# vca_A.net
KiCad netlist of a schematic drawn in Altium Designer
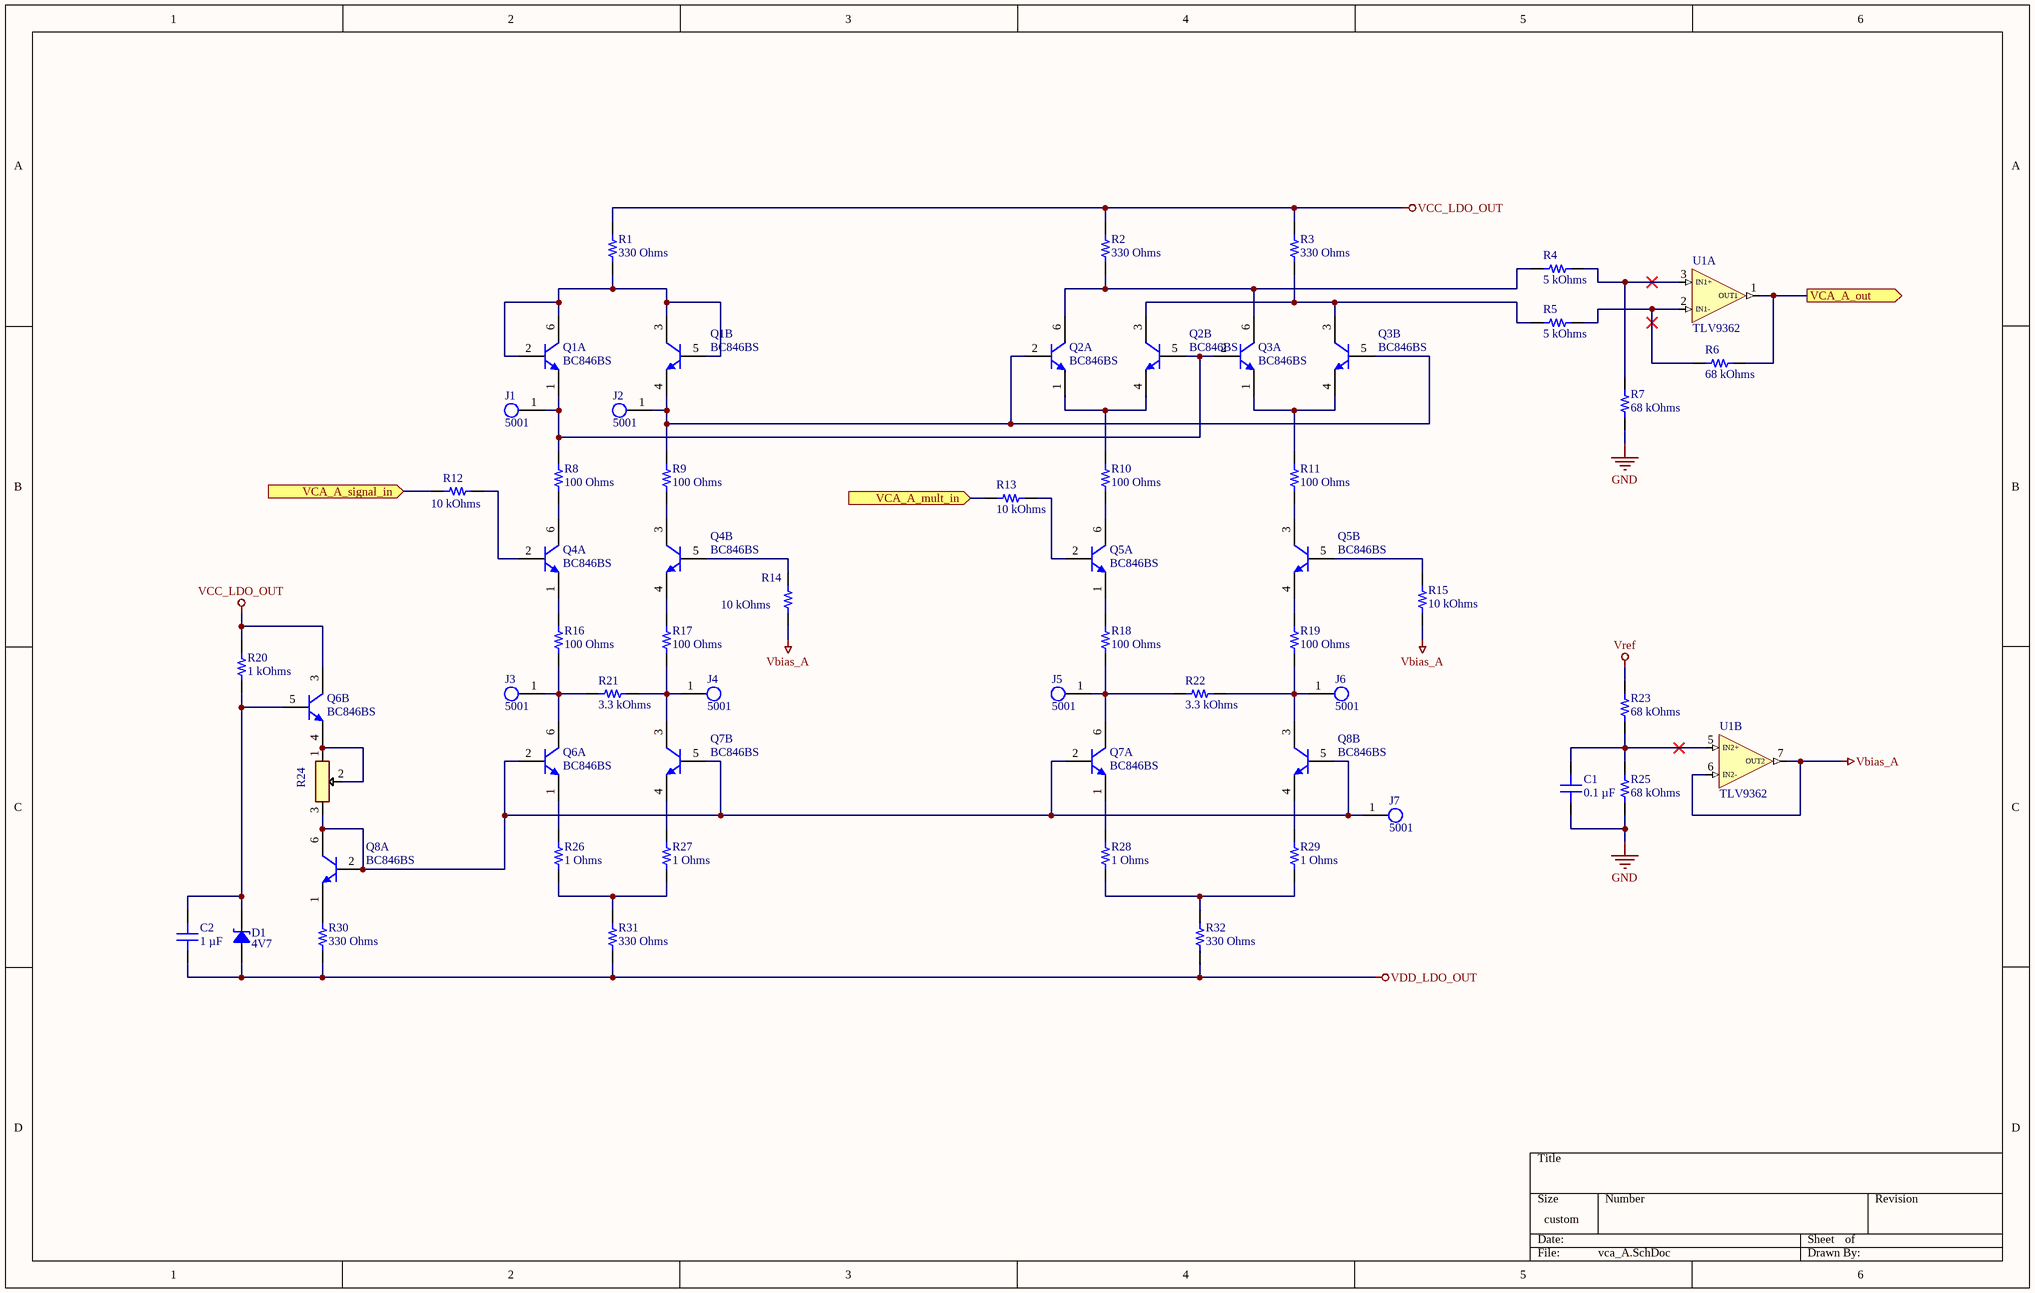
[diagram p0: vca_A.SchDoc]

(export (version "E")
  (design (tool "Eeschema 10.0.6"))
  (components
    (comp (ref "C1")
      (value "0.1 µF")
      (footprint "CAP 1206_3216 - 0.8MM")
      (description "CAP CER 0.1UF 50V X7R 1206")
      (fields
        (field (name "PART NUMBER") "885012208087")
        (field (name "CAPACITANCE") "0.1 µF")
        (field (name "MANUFACTURER") "Würth Elektronik")
      )
      (libsource (lib "Celestial Altium Library - altium_library") (part "Capacitor"))
    )
    (comp (ref "C2")
      (value "1 µF")
      (footprint "CAP 1206_3216 - 0.8MM")
      (description "CAP CER 1UF 50V X7R 1206")
      (fields
        (field (name "PART NUMBER") "885012208093")
        (field (name "CAPACITANCE") "1 µF")
        (field (name "MANUFACTURER") "Würth Elektronik")
      )
      (libsource (lib "Celestial Altium Library - altium_library") (part "Capacitor"))
    )
    (comp (ref "D1") (value "4V7") (footprint "SOD323") (libsource (lib "za_koncar") (part "BZX38450-C4V7X")))
    (comp (ref "J1")
      (value "5001")
      (footprint "FP-5001-MFG")
      (description "PC TEST POINT MINIATURE BLACK")
      (libsource (lib "za_koncar") (part "CMP-2000-05181-2"))
    )
    (comp (ref "J2")
      (value "5001")
      (footprint "FP-5001-MFG")
      (description "PC TEST POINT MINIATURE BLACK")
      (libsource (lib "za_koncar") (part "CMP-2000-05181-2"))
    )
    (comp (ref "J3")
      (value "5001")
      (footprint "FP-5001-MFG")
      (description "PC TEST POINT MINIATURE BLACK")
      (libsource (lib "za_koncar") (part "CMP-2000-05181-2"))
    )
    (comp (ref "J4")
      (value "5001")
      (footprint "FP-5001-MFG")
      (description "PC TEST POINT MINIATURE BLACK")
      (libsource (lib "za_koncar") (part "CMP-2000-05181-2"))
    )
    (comp (ref "J5")
      (value "5001")
      (footprint "FP-5001-MFG")
      (description "PC TEST POINT MINIATURE BLACK")
      (libsource (lib "za_koncar") (part "CMP-2000-05181-2"))
    )
    (comp (ref "J6")
      (value "5001")
      (footprint "FP-5001-MFG")
      (description "PC TEST POINT MINIATURE BLACK")
      (libsource (lib "za_koncar") (part "CMP-2000-05181-2"))
    )
    (comp (ref "J7")
      (value "5001")
      (footprint "FP-5001-MFG")
      (description "PC TEST POINT MINIATURE BLACK")
      (libsource (lib "za_koncar") (part "CMP-2000-05181-2"))
    )
    (comp (ref "Q1")
      (value "BC846BS")
      (footprint "TSOP65P210X110-6N")
      (description "65 V, 100 mA matched NPN/NPN general-purpose transistor")
      (libsource (lib "za_koncar") (part "BC846BS"))
    )
    (comp (ref "Q2")
      (value "BC846BS")
      (footprint "TSOP65P210X110-6N")
      (description "65 V, 100 mA matched NPN/NPN general-purpose transistor")
      (libsource (lib "za_koncar") (part "BC846BS"))
    )
    (comp (ref "Q3")
      (value "BC846BS")
      (footprint "TSOP65P210X110-6N")
      (description "65 V, 100 mA matched NPN/NPN general-purpose transistor")
      (libsource (lib "za_koncar") (part "BC846BS"))
    )
    (comp (ref "Q4")
      (value "BC846BS")
      (footprint "TSOP65P210X110-6N")
      (description "65 V, 100 mA matched NPN/NPN general-purpose transistor")
      (libsource (lib "za_koncar") (part "BC846BS"))
    )
    (comp (ref "Q5")
      (value "BC846BS")
      (footprint "TSOP65P210X110-6N")
      (description "65 V, 100 mA matched NPN/NPN general-purpose transistor")
      (libsource (lib "za_koncar") (part "BC846BS"))
    )
    (comp (ref "Q6")
      (value "BC846BS")
      (footprint "TSOP65P210X110-6N")
      (description "65 V, 100 mA matched NPN/NPN general-purpose transistor")
      (libsource (lib "za_koncar") (part "BC846BS"))
    )
    (comp (ref "Q7")
      (value "BC846BS")
      (footprint "TSOP65P210X110-6N")
      (description "65 V, 100 mA matched NPN/NPN general-purpose transistor")
      (libsource (lib "za_koncar") (part "BC846BS"))
    )
    (comp (ref "Q8")
      (value "BC846BS")
      (footprint "TSOP65P210X110-6N")
      (description "65 V, 100 mA matched NPN/NPN general-purpose transistor")
      (libsource (lib "za_koncar") (part "BC846BS"))
    )
    (comp (ref "R1")
      (value "330 Ohms")
      (footprint "YAGEO RES 1206_3216")
      (description "RES SMD 330 OHM 1% 1/4W 1206")
      (fields (field (name "PART NUMBER") "RT1206FRD07330RL") (field (name "MANUFACTURER") "Yageo"))
      (libsource (lib "Celestial Altium Library - altium_library") (part "Resistor"))
    )
    (comp (ref "R2")
      (value "330 Ohms")
      (footprint "YAGEO RES 1206_3216")
      (description "RES SMD 330 OHM 1% 1/4W 1206")
      (fields (field (name "PART NUMBER") "RT1206FRD07330RL") (field (name "MANUFACTURER") "Yageo"))
      (libsource (lib "Celestial Altium Library - altium_library") (part "Resistor"))
    )
    (comp (ref "R3")
      (value "330 Ohms")
      (footprint "YAGEO RES 1206_3216")
      (description "RES SMD 330 OHM 1% 1/4W 1206")
      (fields (field (name "PART NUMBER") "RT1206FRD07330RL") (field (name "MANUFACTURER") "Yageo"))
      (libsource (lib "Celestial Altium Library - altium_library") (part "Resistor"))
    )
    (comp (ref "R4")
      (value "5 kOhms")
      (footprint "YAGEO RES 1206_3216")
      (description "RES 5K OHM 1% 1/4W 1206")
      (fields (field (name "PART NUMBER") "RT1206FRE075KL") (field (name "MANUFACTURER") "Yageo"))
      (libsource (lib "Celestial Altium Library - altium_library") (part "Resistor"))
    )
    (comp (ref "R5")
      (value "5 kOhms")
      (footprint "YAGEO RES 1206_3216")
      (description "RES 5K OHM 1% 1/4W 1206")
      (fields (field (name "PART NUMBER") "RT1206FRE075KL") (field (name "MANUFACTURER") "Yageo"))
      (libsource (lib "Celestial Altium Library - altium_library") (part "Resistor"))
    )
    (comp (ref "R6")
      (value "68 kOhms")
      (footprint "YAGEO RES 1206_3216")
      (description "RES SMD 68K OHM 1% 1/4W 1206")
      (fields (field (name "PART NUMBER") "RT1206FRE0768KL") (field (name "MANUFACTURER") "Yageo"))
      (libsource (lib "Celestial Altium Library - altium_library") (part "Resistor"))
    )
    (comp (ref "R7")
      (value "68 kOhms")
      (footprint "YAGEO RES 1206_3216")
      (description "RES SMD 68K OHM 1% 1/4W 1206")
      (fields (field (name "PART NUMBER") "RT1206FRE0768KL") (field (name "MANUFACTURER") "Yageo"))
      (libsource (lib "Celestial Altium Library - altium_library") (part "Resistor"))
    )
    (comp (ref "R8")
      (value "100 Ohms")
      (footprint "YAGEO RES 1206_3216")
      (description "RES SMD 100 OHM 1% 1/4W 1206")
      (fields (field (name "PART NUMBER") "RT1206FRD07100RL") (field (name "MANUFACTURER") "Yageo"))
      (libsource (lib "Celestial Altium Library - altium_library") (part "Resistor"))
    )
    (comp (ref "R9")
      (value "100 Ohms")
      (footprint "YAGEO RES 1206_3216")
      (description "RES SMD 100 OHM 1% 1/4W 1206")
      (fields (field (name "PART NUMBER") "RT1206FRD07100RL") (field (name "MANUFACTURER") "Yageo"))
      (libsource (lib "Celestial Altium Library - altium_library") (part "Resistor"))
    )
    (comp (ref "R10")
      (value "100 Ohms")
      (footprint "YAGEO RES 1206_3216")
      (description "RES SMD 100 OHM 1% 1/4W 1206")
      (fields (field (name "PART NUMBER") "RT1206FRD07100RL") (field (name "MANUFACTURER") "Yageo"))
      (libsource (lib "Celestial Altium Library - altium_library") (part "Resistor"))
    )
    (comp (ref "R11")
      (value "100 Ohms")
      (footprint "YAGEO RES 1206_3216")
      (description "RES SMD 100 OHM 1% 1/4W 1206")
      (fields (field (name "PART NUMBER") "RT1206FRD07100RL") (field (name "MANUFACTURER") "Yageo"))
      (libsource (lib "Celestial Altium Library - altium_library") (part "Resistor"))
    )
    (comp (ref "R12")
      (value "10 kOhms")
      (footprint "YAGEO RES 1206_3216")
      (description "RES SMD 10K OHM 1% 1/4W 1206")
      (fields (field (name "PART NUMBER") "RT1206FRE0710KL") (field (name "MANUFACTURER") "Yageo"))
      (libsource (lib "Celestial Altium Library - altium_library") (part "Resistor"))
    )
    (comp (ref "R13")
      (value "10 kOhms")
      (footprint "YAGEO RES 1206_3216")
      (description "RES SMD 10K OHM 1% 1/4W 1206")
      (fields (field (name "PART NUMBER") "RT1206FRE0710KL") (field (name "MANUFACTURER") "Yageo"))
      (libsource (lib "Celestial Altium Library - altium_library") (part "Resistor"))
    )
    (comp (ref "R14")
      (value "10 kOhms")
      (footprint "YAGEO RES 1206_3216")
      (description "RES SMD 10K OHM 1% 1/4W 1206")
      (fields (field (name "PART NUMBER") "RT1206FRE0710KL") (field (name "MANUFACTURER") "Yageo"))
      (libsource (lib "Celestial Altium Library - altium_library") (part "Resistor"))
    )
    (comp (ref "R15")
      (value "10 kOhms")
      (footprint "YAGEO RES 1206_3216")
      (description "RES SMD 10K OHM 1% 1/4W 1206")
      (fields (field (name "PART NUMBER") "RT1206FRE0710KL") (field (name "MANUFACTURER") "Yageo"))
      (libsource (lib "Celestial Altium Library - altium_library") (part "Resistor"))
    )
    (comp (ref "R16")
      (value "100 Ohms")
      (footprint "YAGEO RES 1206_3216")
      (description "RES SMD 100 OHM 1% 1/4W 1206")
      (fields (field (name "PART NUMBER") "RT1206FRD07100RL") (field (name "MANUFACTURER") "Yageo"))
      (libsource (lib "Celestial Altium Library - altium_library") (part "Resistor"))
    )
    (comp (ref "R17")
      (value "100 Ohms")
      (footprint "YAGEO RES 1206_3216")
      (description "RES SMD 100 OHM 1% 1/4W 1206")
      (fields (field (name "PART NUMBER") "RT1206FRD07100RL") (field (name "MANUFACTURER") "Yageo"))
      (libsource (lib "Celestial Altium Library - altium_library") (part "Resistor"))
    )
    (comp (ref "R18")
      (value "100 Ohms")
      (footprint "YAGEO RES 1206_3216")
      (description "RES SMD 100 OHM 1% 1/4W 1206")
      (fields (field (name "PART NUMBER") "RT1206FRD07100RL") (field (name "MANUFACTURER") "Yageo"))
      (libsource (lib "Celestial Altium Library - altium_library") (part "Resistor"))
    )
    (comp (ref "R19")
      (value "100 Ohms")
      (footprint "YAGEO RES 1206_3216")
      (description "RES SMD 100 OHM 1% 1/4W 1206")
      (fields (field (name "PART NUMBER") "RT1206FRD07100RL") (field (name "MANUFACTURER") "Yageo"))
      (libsource (lib "Celestial Altium Library - altium_library") (part "Resistor"))
    )
    (comp (ref "R20")
      (value "1 kOhms")
      (footprint "YAGEO RES 1206_3216")
      (description "RES SMD 1K OHM 1% 1/4W 1206")
      (fields (field (name "PART NUMBER") "RT1206FRE071KL") (field (name "MANUFACTURER") "Yageo"))
      (libsource (lib "Celestial Altium Library - altium_library") (part "Resistor"))
    )
    (comp (ref "R21")
      (value "3.3 kOhms")
      (footprint "YAGEO RES 1206_3216")
      (description "RES SMD 3.3K OHM 1% 1/4W 1206")
      (fields (field (name "PART NUMBER") "RT1206FRE073K3L") (field (name "MANUFACTURER") "Yageo"))
      (libsource (lib "Celestial Altium Library - altium_library") (part "Resistor"))
    )
    (comp (ref "R22")
      (value "3.3 kOhms")
      (footprint "YAGEO RES 1206_3216")
      (description "RES SMD 3.3K OHM 1% 1/4W 1206")
      (fields (field (name "PART NUMBER") "RT1206FRE073K3L") (field (name "MANUFACTURER") "Yageo"))
      (libsource (lib "Celestial Altium Library - altium_library") (part "Resistor"))
    )
    (comp (ref "R23")
      (value "68 kOhms")
      (footprint "YAGEO RES 1206_3216")
      (description "RES SMD 68K OHM 1% 1/4W 1206")
      (fields (field (name "PART NUMBER") "RT1206FRE0768KL") (field (name "MANUFACTURER") "Yageo"))
      (libsource (lib "Celestial Altium Library - altium_library") (part "Resistor"))
    )
    (comp (ref "R24")
      (value "TC33X-2-502G")
      (footprint "TC33X2503E")
      (description "Resistor")
      (fields (field (name "MOUSER PART NUMBER") "652-TC33X-2-502G"))
      (libsource (lib "za_koncar") (part "TC33X-2-502G"))
    )
    (comp (ref "R25")
      (value "68 kOhms")
      (footprint "YAGEO RES 1206_3216")
      (description "RES SMD 68K OHM 1% 1/4W 1206")
      (fields (field (name "PART NUMBER") "RT1206FRE0768KL") (field (name "MANUFACTURER") "Yageo"))
      (libsource (lib "Celestial Altium Library - altium_library") (part "Resistor"))
    )
    (comp (ref "R26")
      (value "1 Ohms")
      (footprint "YAGEO RES 1206_3216")
      (description "RES 1 OHM 0.1% 1/4W 1206")
      (fields (field (name "PART NUMBER") "RT1206BRD071RL") (field (name "MANUFACTURER") "Yageo"))
      (libsource (lib "Celestial Altium Library - altium_library") (part "Resistor"))
    )
    (comp (ref "R27")
      (value "1 Ohms")
      (footprint "YAGEO RES 1206_3216")
      (description "RES 1 OHM 0.1% 1/4W 1206")
      (fields (field (name "PART NUMBER") "RT1206BRD071RL") (field (name "MANUFACTURER") "Yageo"))
      (libsource (lib "Celestial Altium Library - altium_library") (part "Resistor"))
    )
    (comp (ref "R28")
      (value "1 Ohms")
      (footprint "YAGEO RES 1206_3216")
      (description "RES 1 OHM 0.1% 1/4W 1206")
      (fields (field (name "PART NUMBER") "RT1206BRD071RL") (field (name "MANUFACTURER") "Yageo"))
      (libsource (lib "Celestial Altium Library - altium_library") (part "Resistor"))
    )
    (comp (ref "R29")
      (value "1 Ohms")
      (footprint "YAGEO RES 1206_3216")
      (description "RES 1 OHM 0.1% 1/4W 1206")
      (fields (field (name "PART NUMBER") "RT1206BRD071RL") (field (name "MANUFACTURER") "Yageo"))
      (libsource (lib "Celestial Altium Library - altium_library") (part "Resistor"))
    )
    (comp (ref "R30")
      (value "330 Ohms")
      (footprint "YAGEO RES 1206_3216")
      (description "RES SMD 330 OHM 1% 1/4W 1206")
      (fields (field (name "PART NUMBER") "RT1206FRD07330RL") (field (name "MANUFACTURER") "Yageo"))
      (libsource (lib "Celestial Altium Library - altium_library") (part "Resistor"))
    )
    (comp (ref "R31")
      (value "330 Ohms")
      (footprint "YAGEO RES 1206_3216")
      (description "RES SMD 330 OHM 1% 1/4W 1206")
      (fields (field (name "PART NUMBER") "RT1206FRD07330RL") (field (name "MANUFACTURER") "Yageo"))
      (libsource (lib "Celestial Altium Library - altium_library") (part "Resistor"))
    )
    (comp (ref "R32")
      (value "330 Ohms")
      (footprint "YAGEO RES 1206_3216")
      (description "RES SMD 330 OHM 1% 1/4W 1206")
      (fields (field (name "PART NUMBER") "RT1206FRD07330RL") (field (name "MANUFACTURER") "Yageo"))
      (libsource (lib "Celestial Altium Library - altium_library") (part "Resistor"))
    )
    (comp (ref "U1")
      (value "TLV9362")
      (footprint "SOIC8-127P600X175-8N")
      (description "TLV936x 10-MHz, 40-V, RRO, Operational Amplifie")
      (libsource (lib "za_koncar") (part "TLV9362"))
    )
  )
  (nets
    (net (code "1") (name "/VCA_A_mult_in") (class "Default")
      (node (ref "R13") (pin "1") (pinfunction "1_1") (pintype "passive"))
    )
    (net (code "2") (name "/VCA_A_out") (class "Default")
      (node (ref "R6") (pin "1") (pinfunction "1_1") (pintype "passive"))
      (node (ref "U1") (pin "1") (pinfunction "OUT1_1") (pintype "output"))
    )
    (net (code "3") (name "/VCA_A_signal_in") (class "Default")
      (node (ref "R12") (pin "1") (pinfunction "1_1") (pintype "passive"))
    )
    (net (code "4") (name "GND") (class "Default")
      (node (ref "C1") (pin "1") (pinfunction "1_1") (pintype "passive"))
      (node (ref "R25") (pin "1") (pinfunction "1_1") (pintype "passive"))
      (node (ref "R7") (pin "2") (pinfunction "2_2") (pintype "passive"))
    )
    (net (code "5") (name "Net-(Q1A-B1)") (class "Default")
      (node (ref "Q1") (pin "2") (pinfunction "B1_2") (pintype "passive"))
      (node (ref "Q1") (pin "3") (pinfunction "C2_3") (pintype "passive"))
      (node (ref "Q1") (pin "5") (pinfunction "B2_5") (pintype "passive"))
      (node (ref "Q1") (pin "6") (pinfunction "C1_6") (pintype "passive"))
      (node (ref "R1") (pin "1") (pinfunction "1_1") (pintype "passive"))
    )
    (net (code "6") (name "Net-(Q1A-E1)") (class "Default")
      (node (ref "J1") (pin "1") (pinfunction "1_1") (pintype "passive"))
      (node (ref "Q1") (pin "1") (pinfunction "E1_1") (pintype "passive"))
      (node (ref "Q2") (pin "5") (pinfunction "B2_5") (pintype "passive"))
      (node (ref "Q3") (pin "2") (pinfunction "B1_2") (pintype "passive"))
      (node (ref "R8") (pin "2") (pinfunction "2_2") (pintype "passive"))
    )
    (net (code "7") (name "Net-(Q1B-E2)") (class "Default")
      (node (ref "J2") (pin "1") (pinfunction "1_1") (pintype "passive"))
      (node (ref "Q1") (pin "4") (pinfunction "E2_4") (pintype "passive"))
      (node (ref "Q2") (pin "2") (pinfunction "B1_2") (pintype "passive"))
      (node (ref "Q3") (pin "5") (pinfunction "B2_5") (pintype "passive"))
      (node (ref "R9") (pin "2") (pinfunction "2_2") (pintype "passive"))
    )
    (net (code "8") (name "Net-(Q2A-C1)") (class "Default")
      (node (ref "Q2") (pin "6") (pinfunction "C1_6") (pintype "passive"))
      (node (ref "Q3") (pin "6") (pinfunction "C1_6") (pintype "passive"))
      (node (ref "R2") (pin "1") (pinfunction "1_1") (pintype "passive"))
      (node (ref "R4") (pin "2") (pinfunction "2_2") (pintype "passive"))
    )
    (net (code "9") (name "Net-(Q2A-E1)") (class "Default")
      (node (ref "Q2") (pin "1") (pinfunction "E1_1") (pintype "passive"))
      (node (ref "Q2") (pin "4") (pinfunction "E2_4") (pintype "passive"))
      (node (ref "R10") (pin "2") (pinfunction "2_2") (pintype "passive"))
    )
    (net (code "10") (name "Net-(Q2B-C2)") (class "Default")
      (node (ref "Q2") (pin "3") (pinfunction "C2_3") (pintype "passive"))
      (node (ref "Q3") (pin "3") (pinfunction "C2_3") (pintype "passive"))
      (node (ref "R3") (pin "1") (pinfunction "1_1") (pintype "passive"))
      (node (ref "R5") (pin "2") (pinfunction "2_2") (pintype "passive"))
    )
    (net (code "11") (name "Net-(Q3A-E1)") (class "Default")
      (node (ref "Q3") (pin "1") (pinfunction "E1_1") (pintype "passive"))
      (node (ref "Q3") (pin "4") (pinfunction "E2_4") (pintype "passive"))
      (node (ref "R11") (pin "2") (pinfunction "2_2") (pintype "passive"))
    )
    (net (code "12") (name "Net-(Q4A-B1)") (class "Default")
      (node (ref "Q4") (pin "2") (pinfunction "B1_2") (pintype "passive"))
      (node (ref "R12") (pin "2") (pinfunction "2_2") (pintype "passive"))
    )
    (net (code "13") (name "Net-(Q4A-C1)") (class "Default")
      (node (ref "Q4") (pin "6") (pinfunction "C1_6") (pintype "passive"))
      (node (ref "R8") (pin "1") (pinfunction "1_1") (pintype "passive"))
    )
    (net (code "14") (name "Net-(Q4A-E1)") (class "Default")
      (node (ref "Q4") (pin "1") (pinfunction "E1_1") (pintype "passive"))
      (node (ref "R16") (pin "2") (pinfunction "2_2") (pintype "passive"))
    )
    (net (code "15") (name "Net-(Q4B-B2)") (class "Default")
      (node (ref "Q4") (pin "5") (pinfunction "B2_5") (pintype "passive"))
      (node (ref "R14") (pin "2") (pinfunction "2_2") (pintype "passive"))
    )
    (net (code "16") (name "Net-(Q4B-C2)") (class "Default")
      (node (ref "Q4") (pin "3") (pinfunction "C2_3") (pintype "passive"))
      (node (ref "R9") (pin "1") (pinfunction "1_1") (pintype "passive"))
    )
    (net (code "17") (name "Net-(Q4B-E2)") (class "Default")
      (node (ref "Q4") (pin "4") (pinfunction "E2_4") (pintype "passive"))
      (node (ref "R17") (pin "2") (pinfunction "2_2") (pintype "passive"))
    )
    (net (code "18") (name "Net-(Q5A-B1)") (class "Default")
      (node (ref "Q5") (pin "2") (pinfunction "B1_2") (pintype "passive"))
      (node (ref "R13") (pin "2") (pinfunction "2_2") (pintype "passive"))
    )
    (net (code "19") (name "Net-(Q5A-C1)") (class "Default")
      (node (ref "Q5") (pin "6") (pinfunction "C1_6") (pintype "passive"))
      (node (ref "R10") (pin "1") (pinfunction "1_1") (pintype "passive"))
    )
    (net (code "20") (name "Net-(Q5A-E1)") (class "Default")
      (node (ref "Q5") (pin "1") (pinfunction "E1_1") (pintype "passive"))
      (node (ref "R18") (pin "2") (pinfunction "2_2") (pintype "passive"))
    )
    (net (code "21") (name "Net-(Q5B-B2)") (class "Default")
      (node (ref "Q5") (pin "5") (pinfunction "B2_5") (pintype "passive"))
      (node (ref "R15") (pin "2") (pinfunction "2_2") (pintype "passive"))
    )
    (net (code "22") (name "Net-(Q5B-C2)") (class "Default")
      (node (ref "Q5") (pin "3") (pinfunction "C2_3") (pintype "passive"))
      (node (ref "R11") (pin "1") (pinfunction "1_1") (pintype "passive"))
    )
    (net (code "23") (name "Net-(Q5B-E2)") (class "Default")
      (node (ref "Q5") (pin "4") (pinfunction "E2_4") (pintype "passive"))
      (node (ref "R19") (pin "2") (pinfunction "2_2") (pintype "passive"))
    )
    (net (code "24") (name "Net-(Q6A-B1)") (class "Default")
      (node (ref "J7") (pin "1") (pinfunction "1_1") (pintype "passive"))
      (node (ref "Q6") (pin "2") (pinfunction "B1_2") (pintype "passive"))
      (node (ref "Q7") (pin "2") (pinfunction "B1_2") (pintype "passive"))
      (node (ref "Q7") (pin "5") (pinfunction "B2_5") (pintype "passive"))
      (node (ref "Q8") (pin "2") (pinfunction "B1_2") (pintype "passive"))
      (node (ref "Q8") (pin "5") (pinfunction "B2_5") (pintype "passive"))
      (node (ref "Q8") (pin "6") (pinfunction "C1_6") (pintype "passive"))
      (node (ref "R24") (pin "3") (pinfunction "CW_3") (pintype "passive"))
    )
    (net (code "25") (name "Net-(Q6A-C1)") (class "Default")
      (node (ref "J3") (pin "1") (pinfunction "1_1") (pintype "passive"))
      (node (ref "Q6") (pin "6") (pinfunction "C1_6") (pintype "passive"))
      (node (ref "R16") (pin "1") (pinfunction "1_1") (pintype "passive"))
      (node (ref "R21") (pin "2") (pinfunction "2_2") (pintype "passive"))
    )
    (net (code "26") (name "Net-(Q6A-E1)") (class "Default")
      (node (ref "Q6") (pin "1") (pinfunction "E1_1") (pintype "passive"))
      (node (ref "R26") (pin "2") (pinfunction "2_2") (pintype "passive"))
    )
    (net (code "27") (name "Net-(Q6B-B2)") (class "Default")
      (node (ref "C2") (pin "2") (pinfunction "2_2") (pintype "passive"))
      (node (ref "D1") (pin "2") (pinfunction "2_2") (pintype "passive"))
      (node (ref "Q6") (pin "5") (pinfunction "B2_5") (pintype "passive"))
      (node (ref "R20") (pin "1") (pinfunction "1_1") (pintype "passive"))
    )
    (net (code "28") (name "Net-(Q6B-E2)") (class "Default")
      (node (ref "Q6") (pin "4") (pinfunction "E2_4") (pintype "passive"))
      (node (ref "R24") (pin "1") (pinfunction "CCW_1") (pintype "passive"))
      (node (ref "R24") (pin "2") (pinfunction "W_2") (pintype "passive"))
    )
    (net (code "29") (name "Net-(Q7A-C1)") (class "Default")
      (node (ref "J5") (pin "1") (pinfunction "1_1") (pintype "passive"))
      (node (ref "Q7") (pin "6") (pinfunction "C1_6") (pintype "passive"))
      (node (ref "R18") (pin "1") (pinfunction "1_1") (pintype "passive"))
      (node (ref "R22") (pin "2") (pinfunction "2_2") (pintype "passive"))
    )
    (net (code "30") (name "Net-(Q7A-E1)") (class "Default")
      (node (ref "Q7") (pin "1") (pinfunction "E1_1") (pintype "passive"))
      (node (ref "R28") (pin "2") (pinfunction "2_2") (pintype "passive"))
    )
    (net (code "31") (name "Net-(Q7B-C2)") (class "Default")
      (node (ref "J4") (pin "1") (pinfunction "1_1") (pintype "passive"))
      (node (ref "Q7") (pin "3") (pinfunction "C2_3") (pintype "passive"))
      (node (ref "R17") (pin "1") (pinfunction "1_1") (pintype "passive"))
      (node (ref "R21") (pin "1") (pinfunction "1_1") (pintype "passive"))
    )
    (net (code "32") (name "Net-(Q7B-E2)") (class "Default")
      (node (ref "Q7") (pin "4") (pinfunction "E2_4") (pintype "passive"))
      (node (ref "R27") (pin "2") (pinfunction "2_2") (pintype "passive"))
    )
    (net (code "33") (name "Net-(Q8A-E1)") (class "Default")
      (node (ref "Q8") (pin "1") (pinfunction "E1_1") (pintype "passive"))
      (node (ref "R30") (pin "2") (pinfunction "2_2") (pintype "passive"))
    )
    (net (code "34") (name "Net-(Q8B-C2)") (class "Default")
      (node (ref "J6") (pin "1") (pinfunction "1_1") (pintype "passive"))
      (node (ref "Q8") (pin "3") (pinfunction "C2_3") (pintype "passive"))
      (node (ref "R19") (pin "1") (pinfunction "1_1") (pintype "passive"))
      (node (ref "R22") (pin "1") (pinfunction "1_1") (pintype "passive"))
    )
    (net (code "35") (name "Net-(Q8B-E2)") (class "Default")
      (node (ref "Q8") (pin "4") (pinfunction "E2_4") (pintype "passive"))
      (node (ref "R29") (pin "2") (pinfunction "2_2") (pintype "passive"))
    )
    (net (code "36") (name "Net-(R26-Pad1)") (class "Default")
      (node (ref "R26") (pin "1") (pinfunction "1_1") (pintype "passive"))
      (node (ref "R27") (pin "1") (pinfunction "1_1") (pintype "passive"))
      (node (ref "R31") (pin "2") (pinfunction "2_2") (pintype "passive"))
    )
    (net (code "37") (name "Net-(R28-Pad1)") (class "Default")
      (node (ref "R28") (pin "1") (pinfunction "1_1") (pintype "passive"))
      (node (ref "R29") (pin "1") (pinfunction "1_1") (pintype "passive"))
      (node (ref "R32") (pin "2") (pinfunction "2_2") (pintype "passive"))
    )
    (net (code "38") (name "Net-(U1A-IN1+)") (class "Default")
      (node (ref "R4") (pin "1") (pinfunction "1_1") (pintype "passive"))
      (node (ref "R7") (pin "1") (pinfunction "1_1") (pintype "passive"))
      (node (ref "U1") (pin "3") (pinfunction "IN1+_3") (pintype "input"))
    )
    (net (code "39") (name "Net-(U1A-IN1-)") (class "Default")
      (node (ref "R5") (pin "1") (pinfunction "1_1") (pintype "passive"))
      (node (ref "R6") (pin "2") (pinfunction "2_2") (pintype "passive"))
      (node (ref "U1") (pin "2") (pinfunction "IN1-_2") (pintype "input"))
    )
    (net (code "40") (name "Net-(U1B-IN2+)") (class "Default")
      (node (ref "C1") (pin "2") (pinfunction "2_2") (pintype "passive"))
      (node (ref "R23") (pin "1") (pinfunction "1_1") (pintype "passive"))
      (node (ref "R25") (pin "2") (pinfunction "2_2") (pintype "passive"))
      (node (ref "U1") (pin "5") (pinfunction "IN2+_5") (pintype "input"))
    )
    (net (code "41") (name "VCC_LDO_OUT") (class "Default")
      (node (ref "Q6") (pin "3") (pinfunction "C2_3") (pintype "passive"))
      (node (ref "R1") (pin "2") (pinfunction "2_2") (pintype "passive"))
      (node (ref "R2") (pin "2") (pinfunction "2_2") (pintype "passive"))
      (node (ref "R20") (pin "2") (pinfunction "2_2") (pintype "passive"))
      (node (ref "R3") (pin "2") (pinfunction "2_2") (pintype "passive"))
    )
    (net (code "42") (name "VDD_LDO_OUT") (class "Default")
      (node (ref "C2") (pin "1") (pinfunction "1_1") (pintype "passive"))
      (node (ref "D1") (pin "1") (pinfunction "1_1") (pintype "passive"))
      (node (ref "R30") (pin "1") (pinfunction "1_1") (pintype "passive"))
      (node (ref "R31") (pin "1") (pinfunction "1_1") (pintype "passive"))
      (node (ref "R32") (pin "1") (pinfunction "1_1") (pintype "passive"))
    )
    (net (code "43") (name "Vbias_A") (class "Default")
      (node (ref "R14") (pin "1") (pinfunction "1_1") (pintype "passive"))
      (node (ref "R15") (pin "1") (pinfunction "1_1") (pintype "passive"))
      (node (ref "U1") (pin "6") (pinfunction "IN2-_6") (pintype "input"))
      (node (ref "U1") (pin "7") (pinfunction "OUT2_7") (pintype "output"))
    )
    (net (code "44") (name "Vref") (class "Default")
      (node (ref "R23") (pin "2") (pinfunction "2_2") (pintype "passive"))
    )
  )
)
